# PMIC_Block.net
KiCad netlist of a schematic drawn in Altium Designer
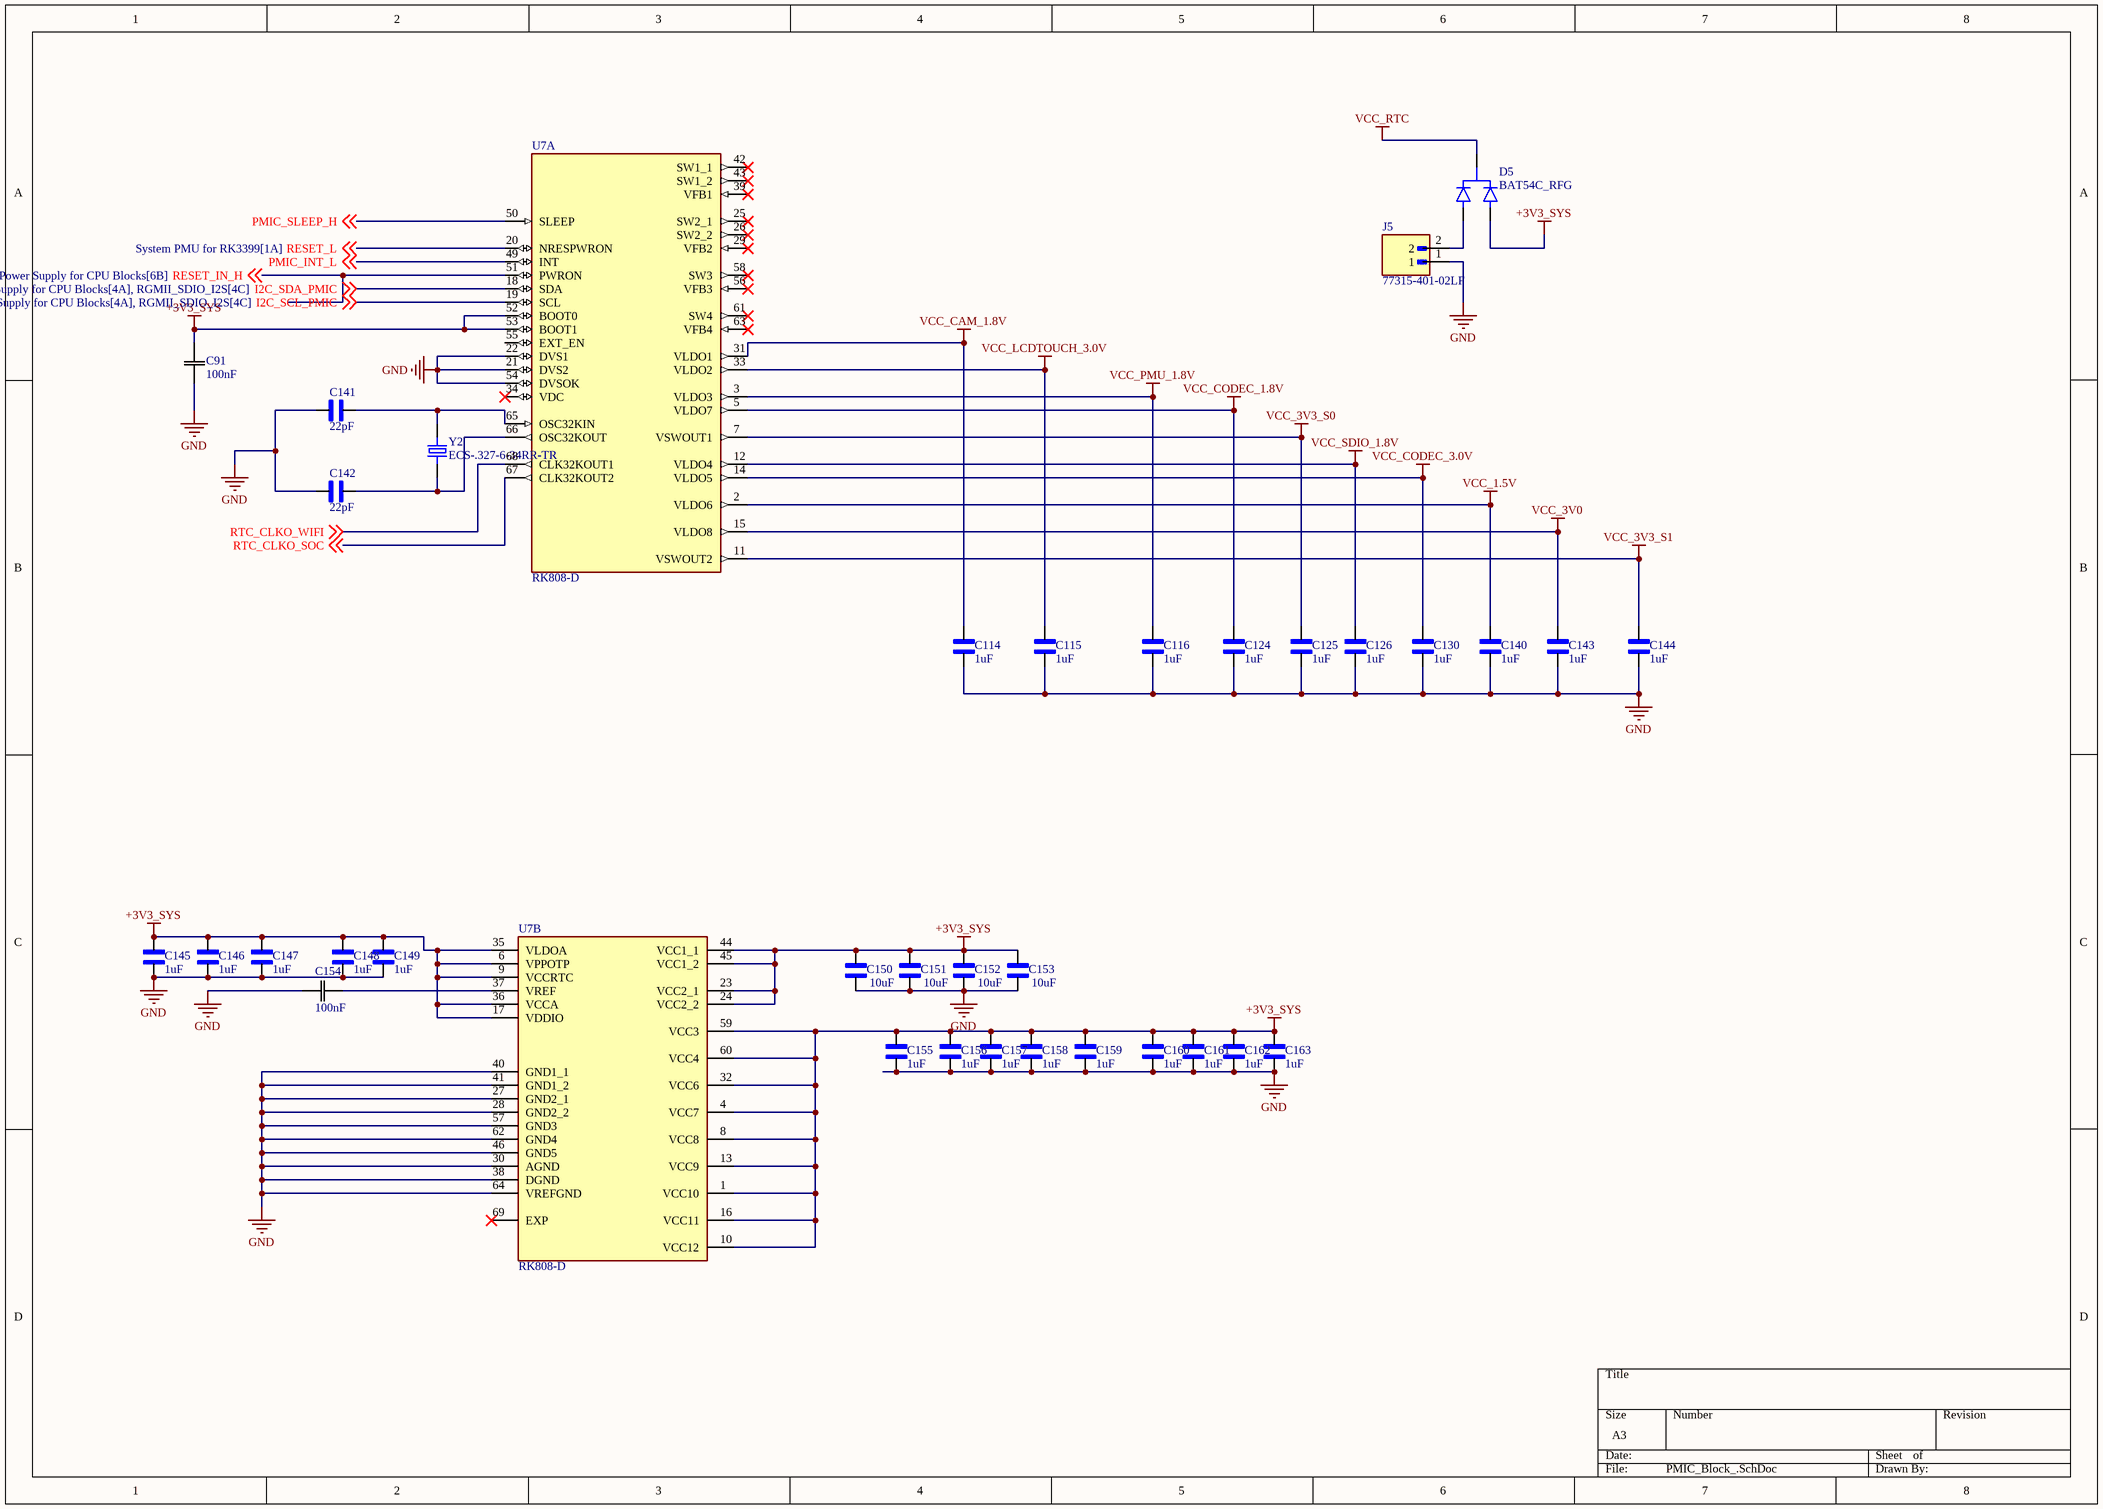
[diagram p0: PMIC_Block_.SchDoc]

(export (version "E")
  (design (tool "Eeschema 10.0.6"))
  (components
    (comp (ref "C91")
      (value "100nF")
      (footprint "CAP_1005_TDK")
      (description "Description")
      (fields
        (field (name "MANUFACTURER_PART_NUMBER") "C1005X7R1H104M050BB")
        (field (name "COPYRIGHT") "Copyright (C) 2025 Ultra Librarian. All rights reserved.")
      )
      (libsource (lib "C1005X7R1H104M050BB") (part "C1005X7R1H104M050BB"))
    )
    (comp (ref "C114")
      (value "1uF")
      (footprint "CAPC1005X56N")
      (description "1 ÂµF Â±10% 10V Ceramic Capacitor X5R 0402 (1005 Metric)")
      (fields (field (name "MF") "AVX") (field (name "MP") "0402ZD105KAT4A"))
      (libsource (lib "0402ZD105KAT4A") (part "0402ZD105KAT4A"))
    )
    (comp (ref "C115")
      (value "1uF")
      (footprint "CAPC1005X56N")
      (description "1 ÂµF Â±10% 10V Ceramic Capacitor X5R 0402 (1005 Metric)")
      (fields (field (name "MF") "AVX") (field (name "MP") "0402ZD105KAT4A"))
      (libsource (lib "0402ZD105KAT4A") (part "0402ZD105KAT4A"))
    )
    (comp (ref "C116")
      (value "1uF")
      (footprint "CAPC1005X56N")
      (description "1 ÂµF Â±10% 10V Ceramic Capacitor X5R 0402 (1005 Metric)")
      (fields (field (name "MF") "AVX") (field (name "MP") "0402ZD105KAT4A"))
      (libsource (lib "0402ZD105KAT4A") (part "0402ZD105KAT4A"))
    )
    (comp (ref "C124")
      (value "1uF")
      (footprint "CAPC1005X56N")
      (description "1 ÂµF Â±10% 10V Ceramic Capacitor X5R 0402 (1005 Metric)")
      (fields (field (name "MF") "AVX") (field (name "MP") "0402ZD105KAT4A"))
      (libsource (lib "0402ZD105KAT4A") (part "0402ZD105KAT4A"))
    )
    (comp (ref "C125")
      (value "1uF")
      (footprint "CAPC1005X56N")
      (description "1 ÂµF Â±10% 10V Ceramic Capacitor X5R 0402 (1005 Metric)")
      (fields (field (name "MF") "AVX") (field (name "MP") "0402ZD105KAT4A"))
      (libsource (lib "0402ZD105KAT4A") (part "0402ZD105KAT4A"))
    )
    (comp (ref "C126")
      (value "1uF")
      (footprint "CAPC1005X56N")
      (description "1 ÂµF Â±10% 10V Ceramic Capacitor X5R 0402 (1005 Metric)")
      (fields (field (name "MF") "AVX") (field (name "MP") "0402ZD105KAT4A"))
      (libsource (lib "0402ZD105KAT4A") (part "0402ZD105KAT4A"))
    )
    (comp (ref "C130")
      (value "1uF")
      (footprint "CAPC1005X56N")
      (description "1 ÂµF Â±10% 10V Ceramic Capacitor X5R 0402 (1005 Metric)")
      (fields (field (name "MF") "AVX") (field (name "MP") "0402ZD105KAT4A"))
      (libsource (lib "0402ZD105KAT4A") (part "0402ZD105KAT4A"))
    )
    (comp (ref "C140")
      (value "1uF")
      (footprint "CAPC1005X56N")
      (description "1 ÂµF Â±10% 10V Ceramic Capacitor X5R 0402 (1005 Metric)")
      (fields (field (name "MF") "AVX") (field (name "MP") "0402ZD105KAT4A"))
      (libsource (lib "0402ZD105KAT4A") (part "0402ZD105KAT4A"))
    )
    (comp (ref "C141")
      (value "22pF")
      (footprint "CAPC2012X140N")
      (description "Capacitor, Ceramic, Cap, 22.0pF, Tol 5%, SMT, 50V, C0G ¦ KEMET C0805C220J5GACTU")
      (fields (field (name "MF") "KEMET") (field (name "MP") "C0805C220J5GACTU"))
      (libsource (lib "C0805C220J5GACTU") (part "C0805C220J5GACTU"))
    )
    (comp (ref "C142")
      (value "22pF")
      (footprint "CAPC2012X140N")
      (description "Capacitor, Ceramic, Cap, 22.0pF, Tol 5%, SMT, 50V, C0G ¦ KEMET C0805C220J5GACTU")
      (fields (field (name "MF") "KEMET") (field (name "MP") "C0805C220J5GACTU"))
      (libsource (lib "C0805C220J5GACTU") (part "C0805C220J5GACTU"))
    )
    (comp (ref "C143")
      (value "1uF")
      (footprint "CAPC1005X56N")
      (description "1 ÂµF Â±10% 10V Ceramic Capacitor X5R 0402 (1005 Metric)")
      (fields (field (name "MF") "AVX") (field (name "MP") "0402ZD105KAT4A"))
      (libsource (lib "0402ZD105KAT4A") (part "0402ZD105KAT4A"))
    )
    (comp (ref "C144")
      (value "1uF")
      (footprint "CAPC1005X56N")
      (description "1 ÂµF Â±10% 10V Ceramic Capacitor X5R 0402 (1005 Metric)")
      (fields (field (name "MF") "AVX") (field (name "MP") "0402ZD105KAT4A"))
      (libsource (lib "0402ZD105KAT4A") (part "0402ZD105KAT4A"))
    )
    (comp (ref "C145")
      (value "1uF")
      (footprint "CAPC1005X56N")
      (description "1 ÂµF Â±10% 10V Ceramic Capacitor X5R 0402 (1005 Metric)")
      (fields (field (name "MF") "AVX") (field (name "MP") "0402ZD105KAT4A"))
      (libsource (lib "0402ZD105KAT4A") (part "0402ZD105KAT4A"))
    )
    (comp (ref "C146")
      (value "1uF")
      (footprint "CAPC1005X56N")
      (description "1 ÂµF Â±10% 10V Ceramic Capacitor X5R 0402 (1005 Metric)")
      (fields (field (name "MF") "AVX") (field (name "MP") "0402ZD105KAT4A"))
      (libsource (lib "0402ZD105KAT4A") (part "0402ZD105KAT4A"))
    )
    (comp (ref "C147")
      (value "1uF")
      (footprint "CAPC1005X56N")
      (description "1 ÂµF Â±10% 10V Ceramic Capacitor X5R 0402 (1005 Metric)")
      (fields (field (name "MF") "AVX") (field (name "MP") "0402ZD105KAT4A"))
      (libsource (lib "0402ZD105KAT4A") (part "0402ZD105KAT4A"))
    )
    (comp (ref "C148")
      (value "1uF")
      (footprint "CAPC1005X56N")
      (description "1 ÂµF Â±10% 10V Ceramic Capacitor X5R 0402 (1005 Metric)")
      (fields (field (name "MF") "AVX") (field (name "MP") "0402ZD105KAT4A"))
      (libsource (lib "0402ZD105KAT4A") (part "0402ZD105KAT4A"))
    )
    (comp (ref "C149")
      (value "1uF")
      (footprint "CAPC1005X56N")
      (description "1 ÂµF Â±10% 10V Ceramic Capacitor X5R 0402 (1005 Metric)")
      (fields (field (name "MF") "AVX") (field (name "MP") "0402ZD105KAT4A"))
      (libsource (lib "0402ZD105KAT4A") (part "0402ZD105KAT4A"))
    )
    (comp (ref "C150")
      (value "10uF")
      (footprint "CAPC1005X70N")
      (description "10 ÂµF Â±20% 6.3V Ceramic Capacitor X5R 0402 (1005 Metric)")
      (fields (field (name "MF") "Samsung") (field (name "MP") "CL05A106MQ5NUNC"))
      (libsource (lib "CL05A106MQ5NUNC") (part "CL05A106MQ5NUNC"))
    )
    (comp (ref "C151")
      (value "10uF")
      (footprint "CAPC1005X70N")
      (description "10 ÂµF Â±20% 6.3V Ceramic Capacitor X5R 0402 (1005 Metric)")
      (fields (field (name "MF") "Samsung") (field (name "MP") "CL05A106MQ5NUNC"))
      (libsource (lib "CL05A106MQ5NUNC") (part "CL05A106MQ5NUNC"))
    )
    (comp (ref "C152")
      (value "10uF")
      (footprint "CAPC1005X70N")
      (description "10 ÂµF Â±20% 6.3V Ceramic Capacitor X5R 0402 (1005 Metric)")
      (fields (field (name "MF") "Samsung") (field (name "MP") "CL05A106MQ5NUNC"))
      (libsource (lib "CL05A106MQ5NUNC") (part "CL05A106MQ5NUNC"))
    )
    (comp (ref "C153")
      (value "10uF")
      (footprint "CAPC1005X70N")
      (description "10 ÂµF Â±20% 6.3V Ceramic Capacitor X5R 0402 (1005 Metric)")
      (fields (field (name "MF") "Samsung") (field (name "MP") "CL05A106MQ5NUNC"))
      (libsource (lib "CL05A106MQ5NUNC") (part "CL05A106MQ5NUNC"))
    )
    (comp (ref "C154")
      (value "100nF")
      (footprint "CAP_1005_TDK")
      (description "Description")
      (fields
        (field (name "MANUFACTURER_PART_NUMBER") "C1005X7R1H104M050BB")
        (field (name "COPYRIGHT") "Copyright (C) 2025 Ultra Librarian. All rights reserved.")
      )
      (libsource (lib "C1005X7R1H104M050BB") (part "C1005X7R1H104M050BB"))
    )
    (comp (ref "C155")
      (value "1uF")
      (footprint "CAPC1005X56N")
      (description "1 ÂµF Â±10% 10V Ceramic Capacitor X5R 0402 (1005 Metric)")
      (fields (field (name "MF") "AVX") (field (name "MP") "0402ZD105KAT4A"))
      (libsource (lib "0402ZD105KAT4A") (part "0402ZD105KAT4A"))
    )
    (comp (ref "C156")
      (value "1uF")
      (footprint "CAPC1005X56N")
      (description "1 ÂµF Â±10% 10V Ceramic Capacitor X5R 0402 (1005 Metric)")
      (fields (field (name "MF") "AVX") (field (name "MP") "0402ZD105KAT4A"))
      (libsource (lib "0402ZD105KAT4A") (part "0402ZD105KAT4A"))
    )
    (comp (ref "C157")
      (value "1uF")
      (footprint "CAPC1005X56N")
      (description "1 ÂµF Â±10% 10V Ceramic Capacitor X5R 0402 (1005 Metric)")
      (fields (field (name "MF") "AVX") (field (name "MP") "0402ZD105KAT4A"))
      (libsource (lib "0402ZD105KAT4A") (part "0402ZD105KAT4A"))
    )
    (comp (ref "C158")
      (value "1uF")
      (footprint "CAPC1005X56N")
      (description "1 ÂµF Â±10% 10V Ceramic Capacitor X5R 0402 (1005 Metric)")
      (fields (field (name "MF") "AVX") (field (name "MP") "0402ZD105KAT4A"))
      (libsource (lib "0402ZD105KAT4A") (part "0402ZD105KAT4A"))
    )
    (comp (ref "C159")
      (value "1uF")
      (footprint "CAPC1005X56N")
      (description "1 ÂµF Â±10% 10V Ceramic Capacitor X5R 0402 (1005 Metric)")
      (fields (field (name "MF") "AVX") (field (name "MP") "0402ZD105KAT4A"))
      (libsource (lib "0402ZD105KAT4A") (part "0402ZD105KAT4A"))
    )
    (comp (ref "C160")
      (value "1uF")
      (footprint "CAPC1005X56N")
      (description "1 ÂµF Â±10% 10V Ceramic Capacitor X5R 0402 (1005 Metric)")
      (fields (field (name "MF") "AVX") (field (name "MP") "0402ZD105KAT4A"))
      (libsource (lib "0402ZD105KAT4A") (part "0402ZD105KAT4A"))
    )
    (comp (ref "C161")
      (value "1uF")
      (footprint "CAPC1005X56N")
      (description "1 ÂµF Â±10% 10V Ceramic Capacitor X5R 0402 (1005 Metric)")
      (fields (field (name "MF") "AVX") (field (name "MP") "0402ZD105KAT4A"))
      (libsource (lib "0402ZD105KAT4A") (part "0402ZD105KAT4A"))
    )
    (comp (ref "C162")
      (value "1uF")
      (footprint "CAPC1005X56N")
      (description "1 ÂµF Â±10% 10V Ceramic Capacitor X5R 0402 (1005 Metric)")
      (fields (field (name "MF") "AVX") (field (name "MP") "0402ZD105KAT4A"))
      (libsource (lib "0402ZD105KAT4A") (part "0402ZD105KAT4A"))
    )
    (comp (ref "C163")
      (value "1uF")
      (footprint "CAPC1005X56N")
      (description "1 ÂµF Â±10% 10V Ceramic Capacitor X5R 0402 (1005 Metric)")
      (fields (field (name "MF") "AVX") (field (name "MP") "0402ZD105KAT4A"))
      (libsource (lib "0402ZD105KAT4A") (part "0402ZD105KAT4A"))
    )
    (comp (ref "D5")
      (value "BAT54C_RFG")
      (footprint "SOT95P237X112-3N")
      (description "SOT-23, 30V, 0.2A, Schottky Diode")
      (fields (field (name "MF") "Taiwan Semiconductor") (field (name "MP") "BAT54C RF"))
      (libsource (lib "BAT54C_RFG") (part "BAT54C_RFG"))
    )
    (comp (ref "J5")
      (value "77315-401-02LF")
      (footprint "AMPHENOL_77315-401-02LF")
      (libsource (lib "77315-401-02LF") (part "77315-401-02LF"))
    )
    (comp (ref "U7")
      (value "RK808-D")
      (footprint "QFN35P700X700X80-69N")
      (description "RK808-D Power Management IC")
      (fields (field (name "MF") "rockchip"))
      (libsource (lib "RK808-D") (part "RK808-D"))
    )
    (comp (ref "Y2")
      (value "ECS-.327-6-34RR-TR")
      (footprint "XTAL_ECS-.327-6-34RR-TR")
      (description "32.768kHz 20ppm Crystal 6pF 20 kOhm -40C ~ 85C Surface Mount 2-SMD, No Lead 3.2 x 1.5")
      (fields (field (name "MF") "ECS Inc."))
      (libsource (lib "ECS-.327-6-34RR-TR") (part "ECS-.327-6-34RR-TR"))
    )
  )
  (nets
    (net (code "1") (name "+3V3_SYS") (class "Default")
      (node (ref "C145") (pin "2") (pinfunction "2_2") (pintype "passive"))
      (node (ref "C146") (pin "2") (pinfunction "2_2") (pintype "passive"))
      (node (ref "C147") (pin "2") (pinfunction "2_2") (pintype "passive"))
      (node (ref "C148") (pin "2") (pinfunction "2_2") (pintype "passive"))
      (node (ref "C149") (pin "2") (pinfunction "2_2") (pintype "passive"))
      (node (ref "C150") (pin "2") (pinfunction "2_2") (pintype "passive"))
      (node (ref "C151") (pin "2") (pinfunction "2_2") (pintype "passive"))
      (node (ref "C152") (pin "2") (pinfunction "2_2") (pintype "passive"))
      (node (ref "C153") (pin "2") (pinfunction "2_2") (pintype "passive"))
      (node (ref "C155") (pin "2") (pinfunction "2_2") (pintype "passive"))
      (node (ref "C156") (pin "2") (pinfunction "2_2") (pintype "passive"))
      (node (ref "C157") (pin "2") (pinfunction "2_2") (pintype "passive"))
      (node (ref "C158") (pin "2") (pinfunction "2_2") (pintype "passive"))
      (node (ref "C159") (pin "2") (pinfunction "2_2") (pintype "passive"))
      (node (ref "C160") (pin "2") (pinfunction "2_2") (pintype "passive"))
      (node (ref "C161") (pin "2") (pinfunction "2_2") (pintype "passive"))
      (node (ref "C162") (pin "2") (pinfunction "2_2") (pintype "passive"))
      (node (ref "C163") (pin "2") (pinfunction "2_2") (pintype "passive"))
      (node (ref "C91") (pin "2") (pinfunction "2_2") (pintype "passive"))
      (node (ref "D5") (pin "2") (pinfunction "2_2") (pintype "passive"))
      (node (ref "U7") (pin "1") (pinfunction "VCC10_1") (pintype "power_in"))
      (node (ref "U7") (pin "10") (pinfunction "VCC12_10") (pintype "power_in"))
      (node (ref "U7") (pin "13") (pinfunction "VCC9_13") (pintype "power_in"))
      (node (ref "U7") (pin "16") (pinfunction "VCC11_16") (pintype "power_in"))
      (node (ref "U7") (pin "17") (pinfunction "VDDIO_17") (pintype "power_in"))
      (node (ref "U7") (pin "23") (pinfunction "VCC2_1_23") (pintype "power_in"))
      (node (ref "U7") (pin "24") (pinfunction "VCC2_2_24") (pintype "power_in"))
      (node (ref "U7") (pin "32") (pinfunction "VCC6_32") (pintype "power_in"))
      (node (ref "U7") (pin "35") (pinfunction "VLDOA_35") (pintype "power_in"))
      (node (ref "U7") (pin "36") (pinfunction "VCCA_36") (pintype "power_in"))
      (node (ref "U7") (pin "4") (pinfunction "VCC7_4") (pintype "power_in"))
      (node (ref "U7") (pin "44") (pinfunction "VCC1_1_44") (pintype "power_in"))
      (node (ref "U7") (pin "45") (pinfunction "VCC1_2_45") (pintype "power_in"))
      (node (ref "U7") (pin "52") (pinfunction "BOOT0_52") (pintype "bidirectional"))
      (node (ref "U7") (pin "53") (pinfunction "BOOT1_53") (pintype "bidirectional"))
      (node (ref "U7") (pin "59") (pinfunction "VCC3_59") (pintype "power_in"))
      (node (ref "U7") (pin "6") (pinfunction "VPPOTP_6") (pintype "power_in"))
      (node (ref "U7") (pin "60") (pinfunction "VCC4_60") (pintype "power_in"))
      (node (ref "U7") (pin "8") (pinfunction "VCC8_8") (pintype "power_in"))
      (node (ref "U7") (pin "9") (pinfunction "VCCRTC_9") (pintype "power_in"))
    )
    (net (code "2") (name "GND") (class "Default")
      (node (ref "C114") (pin "1") (pinfunction "1_1") (pintype "passive"))
      (node (ref "C115") (pin "1") (pinfunction "1_1") (pintype "passive"))
      (node (ref "C116") (pin "1") (pinfunction "1_1") (pintype "passive"))
      (node (ref "C124") (pin "1") (pinfunction "1_1") (pintype "passive"))
      (node (ref "C125") (pin "1") (pinfunction "1_1") (pintype "passive"))
      (node (ref "C126") (pin "1") (pinfunction "1_1") (pintype "passive"))
      (node (ref "C130") (pin "1") (pinfunction "1_1") (pintype "passive"))
      (node (ref "C140") (pin "1") (pinfunction "1_1") (pintype "passive"))
      (node (ref "C141") (pin "2") (pinfunction "2_2") (pintype "passive"))
      (node (ref "C142") (pin "2") (pinfunction "2_2") (pintype "passive"))
      (node (ref "C143") (pin "1") (pinfunction "1_1") (pintype "passive"))
      (node (ref "C144") (pin "1") (pinfunction "1_1") (pintype "passive"))
      (node (ref "C145") (pin "1") (pinfunction "1_1") (pintype "passive"))
      (node (ref "C146") (pin "1") (pinfunction "1_1") (pintype "passive"))
      (node (ref "C147") (pin "1") (pinfunction "1_1") (pintype "passive"))
      (node (ref "C148") (pin "1") (pinfunction "1_1") (pintype "passive"))
      (node (ref "C149") (pin "1") (pinfunction "1_1") (pintype "passive"))
      (node (ref "C150") (pin "1") (pinfunction "1_1") (pintype "passive"))
      (node (ref "C151") (pin "1") (pinfunction "1_1") (pintype "passive"))
      (node (ref "C152") (pin "1") (pinfunction "1_1") (pintype "passive"))
      (node (ref "C153") (pin "1") (pinfunction "1_1") (pintype "passive"))
      (node (ref "C154") (pin "2") (pinfunction "2_2") (pintype "passive"))
      (node (ref "C155") (pin "1") (pinfunction "1_1") (pintype "passive"))
      (node (ref "C156") (pin "1") (pinfunction "1_1") (pintype "passive"))
      (node (ref "C157") (pin "1") (pinfunction "1_1") (pintype "passive"))
      (node (ref "C158") (pin "1") (pinfunction "1_1") (pintype "passive"))
      (node (ref "C159") (pin "1") (pinfunction "1_1") (pintype "passive"))
      (node (ref "C160") (pin "1") (pinfunction "1_1") (pintype "passive"))
      (node (ref "C161") (pin "1") (pinfunction "1_1") (pintype "passive"))
      (node (ref "C162") (pin "1") (pinfunction "1_1") (pintype "passive"))
      (node (ref "C163") (pin "1") (pinfunction "1_1") (pintype "passive"))
      (node (ref "C91") (pin "1") (pinfunction "1_1") (pintype "passive"))
      (node (ref "J5") (pin "1") (pinfunction "1_1") (pintype "passive"))
      (node (ref "U7") (pin "21") (pinfunction "DVS2_21") (pintype "bidirectional"))
      (node (ref "U7") (pin "22") (pinfunction "DVS1_22") (pintype "bidirectional"))
      (node (ref "U7") (pin "27") (pinfunction "GND2_1_27") (pintype "power_in"))
      (node (ref "U7") (pin "28") (pinfunction "GND2_2_28") (pintype "power_in"))
      (node (ref "U7") (pin "30") (pinfunction "AGND_30") (pintype "power_in"))
      (node (ref "U7") (pin "38") (pinfunction "DGND_38") (pintype "power_in"))
      (node (ref "U7") (pin "40") (pinfunction "GND1_1_40") (pintype "power_in"))
      (node (ref "U7") (pin "41") (pinfunction "GND1_2_41") (pintype "power_in"))
      (node (ref "U7") (pin "46") (pinfunction "GND5_46") (pintype "power_in"))
      (node (ref "U7") (pin "54") (pinfunction "DVSOK_54") (pintype "bidirectional"))
      (node (ref "U7") (pin "57") (pinfunction "GND3_57") (pintype "power_in"))
      (node (ref "U7") (pin "62") (pinfunction "GND4_62") (pintype "power_in"))
      (node (ref "U7") (pin "64") (pinfunction "VREFGND_64") (pintype "power_in"))
    )
    (net (code "3") (name "I2C_SCL_PMIC") (class "Default")
      (node (ref "U7") (pin "19") (pinfunction "SCL_19") (pintype "bidirectional"))
    )
    (net (code "4") (name "I2C_SDA_PMIC") (class "Default")
      (node (ref "U7") (pin "18") (pinfunction "SDA_18") (pintype "bidirectional"))
    )
    (net (code "5") (name "Net-(D5-Pad1)") (class "Default")
      (node (ref "D5") (pin "1") (pinfunction "1_1") (pintype "passive"))
      (node (ref "J5") (pin "2") (pinfunction "2_2") (pintype "passive"))
    )
    (net (code "6") (name "Net-(U7A-OSC32KIN)") (class "Default")
      (node (ref "C141") (pin "1") (pinfunction "1_1") (pintype "passive"))
      (node (ref "U7") (pin "65") (pinfunction "OSC32KIN_65") (pintype "input"))
      (node (ref "Y2") (pin "2") (pinfunction "O/I_2") (pintype "passive"))
    )
    (net (code "7") (name "Net-(U7A-OSC32KOUT)") (class "Default")
      (node (ref "C142") (pin "1") (pinfunction "1_1") (pintype "passive"))
      (node (ref "U7") (pin "66") (pinfunction "OSC32KOUT_66") (pintype "output"))
      (node (ref "Y2") (pin "1") (pinfunction "I/O_1") (pintype "passive"))
    )
    (net (code "8") (name "Net-(U7B-VREF)") (class "Default")
      (node (ref "C154") (pin "1") (pinfunction "1_1") (pintype "passive"))
      (node (ref "U7") (pin "37") (pinfunction "VREF_37") (pintype "power_in"))
    )
    (net (code "9") (name "PMIC_INT_L") (class "Default")
      (node (ref "U7") (pin "49") (pinfunction "INT_49") (pintype "bidirectional"))
    )
    (net (code "10") (name "PMIC_SLEEP_H") (class "Default")
      (node (ref "U7") (pin "50") (pinfunction "SLEEP_50") (pintype "input"))
    )
    (net (code "11") (name "RESET_IN_H") (class "Default")
      (node (ref "U7") (pin "51") (pinfunction "PWRON_51") (pintype "bidirectional"))
    )
    (net (code "12") (name "RESET_L") (class "Default")
      (node (ref "U7") (pin "20") (pinfunction "NRESPWRON_20") (pintype "bidirectional"))
    )
    (net (code "13") (name "RTC_CLKO_SOC") (class "Default")
      (node (ref "U7") (pin "67") (pinfunction "CLK32KOUT2_67") (pintype "output"))
    )
    (net (code "14") (name "RTC_CLKO_WIFI") (class "Default")
      (node (ref "U7") (pin "68") (pinfunction "CLK32KOUT1_68") (pintype "output"))
    )
    (net (code "15") (name "VCC_1.5V") (class "Default")
      (node (ref "C140") (pin "2") (pinfunction "2_2") (pintype "passive"))
      (node (ref "U7") (pin "2") (pinfunction "VLDO6_2") (pintype "output"))
    )
    (net (code "16") (name "VCC_3V0") (class "Default")
      (node (ref "C143") (pin "2") (pinfunction "2_2") (pintype "passive"))
      (node (ref "U7") (pin "15") (pinfunction "VLDO8_15") (pintype "output"))
    )
    (net (code "17") (name "VCC_3V3_S0") (class "Default")
      (node (ref "C125") (pin "2") (pinfunction "2_2") (pintype "passive"))
      (node (ref "U7") (pin "7") (pinfunction "VSWOUT1_7") (pintype "output"))
    )
    (net (code "18") (name "VCC_3V3_S1") (class "Default")
      (node (ref "C144") (pin "2") (pinfunction "2_2") (pintype "passive"))
      (node (ref "U7") (pin "11") (pinfunction "VSWOUT2_11") (pintype "output"))
    )
    (net (code "19") (name "VCC_CAM_1.8V") (class "Default")
      (node (ref "C114") (pin "2") (pinfunction "2_2") (pintype "passive"))
      (node (ref "U7") (pin "31") (pinfunction "VLDO1_31") (pintype "output"))
    )
    (net (code "20") (name "VCC_CODEC_1.8V") (class "Default")
      (node (ref "C124") (pin "2") (pinfunction "2_2") (pintype "passive"))
      (node (ref "U7") (pin "5") (pinfunction "VLDO7_5") (pintype "output"))
    )
    (net (code "21") (name "VCC_CODEC_3.0V") (class "Default")
      (node (ref "C130") (pin "2") (pinfunction "2_2") (pintype "passive"))
      (node (ref "U7") (pin "14") (pinfunction "VLDO5_14") (pintype "output"))
    )
    (net (code "22") (name "VCC_LCDTOUCH_3.0V") (class "Default")
      (node (ref "C115") (pin "2") (pinfunction "2_2") (pintype "passive"))
      (node (ref "U7") (pin "33") (pinfunction "VLDO2_33") (pintype "output"))
    )
    (net (code "23") (name "VCC_PMU_1.8V") (class "Default")
      (node (ref "C116") (pin "2") (pinfunction "2_2") (pintype "passive"))
      (node (ref "U7") (pin "3") (pinfunction "VLDO3_3") (pintype "output"))
    )
    (net (code "24") (name "VCC_RTC") (class "Default")
      (node (ref "D5") (pin "3") (pinfunction "3_3") (pintype "passive"))
    )
    (net (code "25") (name "VCC_SDIO_1.8V") (class "Default")
      (node (ref "C126") (pin "2") (pinfunction "2_2") (pintype "passive"))
      (node (ref "U7") (pin "12") (pinfunction "VLDO4_12") (pintype "output"))
    )
    (net (code "26") (name "unconnected-(U7A-EXT_EN-Pad55)") (class "Default")
      (node (ref "U7") (pin "55") (pinfunction "EXT_EN_55") (pintype "bidirectional"))
    )
    (net (code "27") (name "unconnected-(U7A-SW1_1-Pad42)") (class "Default")
      (node (ref "U7") (pin "42") (pinfunction "SW1_1_42") (pintype "output+no_connect"))
    )
    (net (code "28") (name "unconnected-(U7A-SW1_2-Pad43)") (class "Default")
      (node (ref "U7") (pin "43") (pinfunction "SW1_2_43") (pintype "output+no_connect"))
    )
    (net (code "29") (name "unconnected-(U7A-SW2_1-Pad25)") (class "Default")
      (node (ref "U7") (pin "25") (pinfunction "SW2_1_25") (pintype "output+no_connect"))
    )
    (net (code "30") (name "unconnected-(U7A-SW2_2-Pad26)") (class "Default")
      (node (ref "U7") (pin "26") (pinfunction "SW2_2_26") (pintype "output+no_connect"))
    )
    (net (code "31") (name "unconnected-(U7A-SW3-Pad58)") (class "Default")
      (node (ref "U7") (pin "58") (pinfunction "SW3_58") (pintype "output+no_connect"))
    )
    (net (code "32") (name "unconnected-(U7A-SW4-Pad61)") (class "Default")
      (node (ref "U7") (pin "61") (pinfunction "SW4_61") (pintype "output+no_connect"))
    )
    (net (code "33") (name "unconnected-(U7A-VDC-Pad34)") (class "Default")
      (node (ref "U7") (pin "34") (pinfunction "VDC_34") (pintype "bidirectional+no_connect"))
    )
    (net (code "34") (name "unconnected-(U7A-VFB1-Pad39)") (class "Default")
      (node (ref "U7") (pin "39") (pinfunction "VFB1_39") (pintype "input+no_connect"))
    )
    (net (code "35") (name "unconnected-(U7A-VFB2-Pad29)") (class "Default")
      (node (ref "U7") (pin "29") (pinfunction "VFB2_29") (pintype "input+no_connect"))
    )
    (net (code "36") (name "unconnected-(U7A-VFB3-Pad56)") (class "Default")
      (node (ref "U7") (pin "56") (pinfunction "VFB3_56") (pintype "input+no_connect"))
    )
    (net (code "37") (name "unconnected-(U7A-VFB4-Pad63)") (class "Default")
      (node (ref "U7") (pin "63") (pinfunction "VFB4_63") (pintype "input+no_connect"))
    )
    (net (code "38") (name "unconnected-(U7B-EXP-Pad69)") (class "Default")
      (node (ref "U7") (pin "69") (pinfunction "EXP_69") (pintype "power_in+no_connect"))
    )
  )
)
